# ProstheticController.net
KiCad netlist of a schematic drawn in Altium Designer
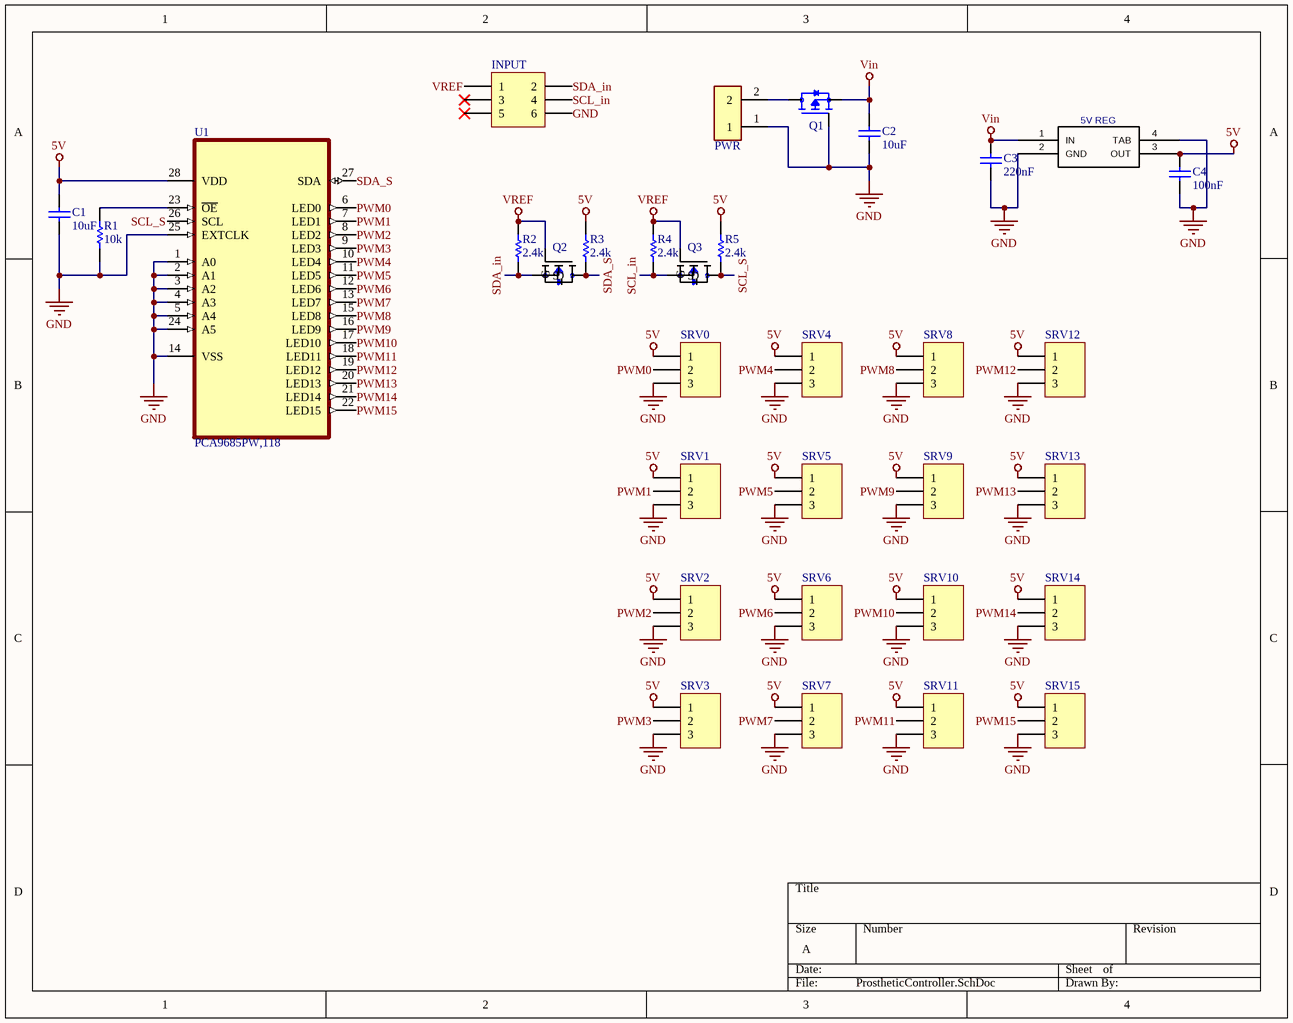
[diagram p0: ProstheticController.SchDoc]

(export (version "E")
  (design (tool "Eeschema 10.0.6"))
  (components
    (comp (ref "5V REG")
      (value "LM340SX-5.0/NOPB")
      (footprint "TS3B_TEX")
      (libsource (lib "5V_REG") (part "LM340SX-5.0/NOPB"))
    )
    (comp (ref "C1")
      (value "10uF")
      (footprint "0805-CAP")
      (description "Capacitor")
      (libsource (lib "Cap") (part "Cap"))
    )
    (comp (ref "C2")
      (value "10uF")
      (footprint "0805-CAP")
      (description "Capacitor")
      (libsource (lib "Cap") (part "Cap"))
    )
    (comp (ref "C3")
      (value "220nF")
      (footprint "0805-CAP")
      (description "Capacitor")
      (libsource (lib "Cap") (part "Cap"))
    )
    (comp (ref "C4")
      (value "100nF")
      (footprint "0805-CAP")
      (description "Capacitor")
      (libsource (lib "Cap") (part "Cap"))
    )
    (comp (ref "INPUT")
      (value "Header 3X2")
      (footprint "HDR2X3")
      (description "Header, 3-Pin, Dual row")
      (fields (field (name "PUBLISHER") "Altium Limited"))
      (libsource (lib "Miscellaneous Connectors") (part "Header 3X2"))
    )
    (comp (ref "PWR")
      (value "PWR")
      (footprint "OST_OSTTE020161")
      (fields (field (name "MP") "OSTTE020161") (field (name "MF") "On Shore"))
      (libsource (lib "Header2Pin") (part "OSTTE020161"))
    )
    (comp (ref "Q1")
      (value "AOD417")
      (footprint "DPAK228P994X240_3N")
      (description "P-Channel 30V 25A _Ta_ 2.5W _Ta_, 50W _Tc_ Surface Mount TO-252, _D-Pak_")
      (fields (field (name "MF") "Alpha &"))
      (libsource (lib "AOD417") (part "AOD417"))
    )
    (comp (ref "Q2")
      (value "BSS138")
      (footprint "*BSS138_BSS138(Primary)")
      (description "N-Channel 50V 220mA _Ta_ 360mW _Ta_ Surface Mount Die")
      (fields (field (name "MF") "MICROSS/On Semiconductor"))
      (libsource (lib "BSS138") (part "BSS138"))
    )
    (comp (ref "Q3")
      (value "BSS138")
      (footprint "*BSS138_BSS138(Primary)")
      (description "N-Channel 50V 220mA _Ta_ 360mW _Ta_ Surface Mount Die")
      (fields (field (name "MF") "MICROSS/On Semiconductor"))
      (libsource (lib "BSS138") (part "BSS138"))
    )
    (comp (ref "R1")
      (value "10k")
      (footprint "0805-RES")
      (description "Resistor")
      (libsource (lib "ResBasic") (part "ResBasic"))
    )
    (comp (ref "R2")
      (value "2.4k")
      (footprint "0805-RES")
      (description "Resistor")
      (libsource (lib "ResBasic") (part "ResBasic"))
    )
    (comp (ref "R3")
      (value "2.4k")
      (footprint "0805-RES")
      (description "Resistor")
      (libsource (lib "ResBasic") (part "ResBasic"))
    )
    (comp (ref "R4")
      (value "2.4k")
      (footprint "0805-RES")
      (description "Resistor")
      (libsource (lib "ResBasic") (part "ResBasic"))
    )
    (comp (ref "R5")
      (value "2.4k")
      (footprint "0805-RES")
      (description "Resistor")
      (libsource (lib "ResBasic") (part "ResBasic"))
    )
    (comp (ref "SRV0")
      (value "Header 3")
      (footprint "HDR1X3")
      (description "Header, 3-Pin")
      (fields (field (name "PUBLISHER") "Altium Limited"))
      (libsource (lib "Miscellaneous Connectors") (part "Header 3"))
    )
    (comp (ref "SRV1")
      (value "Header 3")
      (footprint "HDR1X3")
      (description "Header, 3-Pin")
      (fields (field (name "PUBLISHER") "Altium Limited"))
      (libsource (lib "Miscellaneous Connectors") (part "Header 3"))
    )
    (comp (ref "SRV2")
      (value "Header 3")
      (footprint "HDR1X3")
      (description "Header, 3-Pin")
      (fields (field (name "PUBLISHER") "Altium Limited"))
      (libsource (lib "Miscellaneous Connectors") (part "Header 3"))
    )
    (comp (ref "SRV3")
      (value "Header 3")
      (footprint "HDR1X3")
      (description "Header, 3-Pin")
      (fields (field (name "PUBLISHER") "Altium Limited"))
      (libsource (lib "Miscellaneous Connectors") (part "Header 3"))
    )
    (comp (ref "SRV4")
      (value "Header 3")
      (footprint "HDR1X3")
      (description "Header, 3-Pin")
      (fields (field (name "PUBLISHER") "Altium Limited"))
      (libsource (lib "Miscellaneous Connectors") (part "Header 3"))
    )
    (comp (ref "SRV5")
      (value "Header 3")
      (footprint "HDR1X3")
      (description "Header, 3-Pin")
      (fields (field (name "PUBLISHER") "Altium Limited"))
      (libsource (lib "Miscellaneous Connectors") (part "Header 3"))
    )
    (comp (ref "SRV6")
      (value "Header 3")
      (footprint "HDR1X3")
      (description "Header, 3-Pin")
      (fields (field (name "PUBLISHER") "Altium Limited"))
      (libsource (lib "Miscellaneous Connectors") (part "Header 3"))
    )
    (comp (ref "SRV7")
      (value "Header 3")
      (footprint "HDR1X3")
      (description "Header, 3-Pin")
      (fields (field (name "PUBLISHER") "Altium Limited"))
      (libsource (lib "Miscellaneous Connectors") (part "Header 3"))
    )
    (comp (ref "SRV8")
      (value "Header 3")
      (footprint "HDR1X3")
      (description "Header, 3-Pin")
      (fields (field (name "PUBLISHER") "Altium Limited"))
      (libsource (lib "Miscellaneous Connectors") (part "Header 3"))
    )
    (comp (ref "SRV9")
      (value "Header 3")
      (footprint "HDR1X3")
      (description "Header, 3-Pin")
      (fields (field (name "PUBLISHER") "Altium Limited"))
      (libsource (lib "Miscellaneous Connectors") (part "Header 3"))
    )
    (comp (ref "SRV10")
      (value "Header 3")
      (footprint "HDR1X3")
      (description "Header, 3-Pin")
      (fields (field (name "PUBLISHER") "Altium Limited"))
      (libsource (lib "Miscellaneous Connectors") (part "Header 3"))
    )
    (comp (ref "SRV11")
      (value "Header 3")
      (footprint "HDR1X3")
      (description "Header, 3-Pin")
      (fields (field (name "PUBLISHER") "Altium Limited"))
      (libsource (lib "Miscellaneous Connectors") (part "Header 3"))
    )
    (comp (ref "SRV12")
      (value "Header 3")
      (footprint "HDR1X3")
      (description "Header, 3-Pin")
      (fields (field (name "PUBLISHER") "Altium Limited"))
      (libsource (lib "Miscellaneous Connectors") (part "Header 3"))
    )
    (comp (ref "SRV13")
      (value "Header 3")
      (footprint "HDR1X3")
      (description "Header, 3-Pin")
      (fields (field (name "PUBLISHER") "Altium Limited"))
      (libsource (lib "Miscellaneous Connectors") (part "Header 3"))
    )
    (comp (ref "SRV14")
      (value "Header 3")
      (footprint "HDR1X3")
      (description "Header, 3-Pin")
      (fields (field (name "PUBLISHER") "Altium Limited"))
      (libsource (lib "Miscellaneous Connectors") (part "Header 3"))
    )
    (comp (ref "SRV15")
      (value "Header 3")
      (footprint "HDR1X3")
      (description "Header, 3-Pin")
      (fields (field (name "PUBLISHER") "Altium Limited"))
      (libsource (lib "Miscellaneous Connectors") (part "Header 3"))
    )
    (comp (ref "U1")
      (value "PCA9685PW,118")
      (footprint "SOP65P640X110-28N")
      (description "LED Driver IC 16 Output Linear PWM Dimming 25mA 28-TSSOP")
      (fields (field (name "DIGI-KEY_PART_NUMBER") "568-11925-1-ND") (field (name "MF") "NXP USA"))
      (libsource (lib "SERVO_DRIVER") (part "PCA9685PW,118"))
    )
  )
  (nets
    (net (code "1") (name "/PWM0") (class "Default")
      (node (ref "SRV0") (pin "2") (pinfunction "2_2") (pintype "passive"))
      (node (ref "U1") (pin "6") (pinfunction "LED0_6") (pintype "output"))
    )
    (net (code "2") (name "/PWM1") (class "Default")
      (node (ref "SRV1") (pin "2") (pinfunction "2_2") (pintype "passive"))
      (node (ref "U1") (pin "7") (pinfunction "LED1_7") (pintype "output"))
    )
    (net (code "3") (name "/PWM2") (class "Default")
      (node (ref "SRV2") (pin "2") (pinfunction "2_2") (pintype "passive"))
      (node (ref "U1") (pin "8") (pinfunction "LED2_8") (pintype "output"))
    )
    (net (code "4") (name "/PWM3") (class "Default")
      (node (ref "SRV3") (pin "2") (pinfunction "2_2") (pintype "passive"))
      (node (ref "U1") (pin "9") (pinfunction "LED3_9") (pintype "output"))
    )
    (net (code "5") (name "/PWM4") (class "Default")
      (node (ref "SRV4") (pin "2") (pinfunction "2_2") (pintype "passive"))
      (node (ref "U1") (pin "10") (pinfunction "LED4_10") (pintype "output"))
    )
    (net (code "6") (name "/PWM5") (class "Default")
      (node (ref "SRV5") (pin "2") (pinfunction "2_2") (pintype "passive"))
      (node (ref "U1") (pin "11") (pinfunction "LED5_11") (pintype "output"))
    )
    (net (code "7") (name "/PWM6") (class "Default")
      (node (ref "SRV6") (pin "2") (pinfunction "2_2") (pintype "passive"))
      (node (ref "U1") (pin "12") (pinfunction "LED6_12") (pintype "output"))
    )
    (net (code "8") (name "/PWM7") (class "Default")
      (node (ref "SRV7") (pin "2") (pinfunction "2_2") (pintype "passive"))
      (node (ref "U1") (pin "13") (pinfunction "LED7_13") (pintype "output"))
    )
    (net (code "9") (name "/PWM8") (class "Default")
      (node (ref "SRV8") (pin "2") (pinfunction "2_2") (pintype "passive"))
      (node (ref "U1") (pin "15") (pinfunction "LED8_15") (pintype "output"))
    )
    (net (code "10") (name "/PWM9") (class "Default")
      (node (ref "SRV9") (pin "2") (pinfunction "2_2") (pintype "passive"))
      (node (ref "U1") (pin "16") (pinfunction "LED9_16") (pintype "output"))
    )
    (net (code "11") (name "/PWM10") (class "Default")
      (node (ref "SRV10") (pin "2") (pinfunction "2_2") (pintype "passive"))
      (node (ref "U1") (pin "17") (pinfunction "LED10_17") (pintype "output"))
    )
    (net (code "12") (name "/PWM11") (class "Default")
      (node (ref "SRV11") (pin "2") (pinfunction "2_2") (pintype "passive"))
      (node (ref "U1") (pin "18") (pinfunction "LED11_18") (pintype "output"))
    )
    (net (code "13") (name "/PWM12") (class "Default")
      (node (ref "SRV12") (pin "2") (pinfunction "2_2") (pintype "passive"))
      (node (ref "U1") (pin "19") (pinfunction "LED12_19") (pintype "output"))
    )
    (net (code "14") (name "/PWM13") (class "Default")
      (node (ref "SRV13") (pin "2") (pinfunction "2_2") (pintype "passive"))
      (node (ref "U1") (pin "20") (pinfunction "LED13_20") (pintype "output"))
    )
    (net (code "15") (name "/PWM14") (class "Default")
      (node (ref "SRV14") (pin "2") (pinfunction "2_2") (pintype "passive"))
      (node (ref "U1") (pin "21") (pinfunction "LED14_21") (pintype "output"))
    )
    (net (code "16") (name "/PWM15") (class "Default")
      (node (ref "SRV15") (pin "2") (pinfunction "2_2") (pintype "passive"))
      (node (ref "U1") (pin "22") (pinfunction "LED15_22") (pintype "output"))
    )
    (net (code "17") (name "/SCL_S") (class "Default")
      (node (ref "Q3") (pin "D") (pinfunction "D_D") (pintype "passive"))
      (node (ref "R5") (pin "1") (pinfunction "1_1") (pintype "passive"))
      (node (ref "U1") (pin "26") (pinfunction "SCL_26") (pintype "input"))
    )
    (net (code "18") (name "/SCL_in") (class "Default")
      (node (ref "INPUT") (pin "4") (pinfunction "4_4") (pintype "passive"))
      (node (ref "Q3") (pin "S") (pinfunction "S_S") (pintype "passive"))
      (node (ref "R4") (pin "1") (pinfunction "1_1") (pintype "passive"))
    )
    (net (code "19") (name "/SDA_S") (class "Default")
      (node (ref "Q2") (pin "D") (pinfunction "D_D") (pintype "passive"))
      (node (ref "R3") (pin "1") (pinfunction "1_1") (pintype "passive"))
      (node (ref "U1") (pin "27") (pinfunction "SDA_27") (pintype "bidirectional"))
    )
    (net (code "20") (name "/SDA_in") (class "Default")
      (node (ref "INPUT") (pin "2") (pinfunction "2_2") (pintype "passive"))
      (node (ref "Q2") (pin "S") (pinfunction "S_S") (pintype "passive"))
      (node (ref "R2") (pin "1") (pinfunction "1_1") (pintype "passive"))
    )
    (net (code "21") (name "5V") (class "Default")
      (node (ref "5V REG") (pin "3") (pinfunction "OUT_3") (pintype "power_in"))
      (node (ref "C1") (pin "2") (pinfunction "2_2") (pintype "passive"))
      (node (ref "C4") (pin "2") (pinfunction "2_2") (pintype "passive"))
      (node (ref "R3") (pin "2") (pinfunction "2_2") (pintype "passive"))
      (node (ref "R5") (pin "2") (pinfunction "2_2") (pintype "passive"))
      (node (ref "SRV0") (pin "1") (pinfunction "1_1") (pintype "passive"))
      (node (ref "SRV1") (pin "1") (pinfunction "1_1") (pintype "passive"))
      (node (ref "SRV10") (pin "1") (pinfunction "1_1") (pintype "passive"))
      (node (ref "SRV11") (pin "1") (pinfunction "1_1") (pintype "passive"))
      (node (ref "SRV12") (pin "1") (pinfunction "1_1") (pintype "passive"))
      (node (ref "SRV13") (pin "1") (pinfunction "1_1") (pintype "passive"))
      (node (ref "SRV14") (pin "1") (pinfunction "1_1") (pintype "passive"))
      (node (ref "SRV15") (pin "1") (pinfunction "1_1") (pintype "passive"))
      (node (ref "SRV2") (pin "1") (pinfunction "1_1") (pintype "passive"))
      (node (ref "SRV3") (pin "1") (pinfunction "1_1") (pintype "passive"))
      (node (ref "SRV4") (pin "1") (pinfunction "1_1") (pintype "passive"))
      (node (ref "SRV5") (pin "1") (pinfunction "1_1") (pintype "passive"))
      (node (ref "SRV6") (pin "1") (pinfunction "1_1") (pintype "passive"))
      (node (ref "SRV7") (pin "1") (pinfunction "1_1") (pintype "passive"))
      (node (ref "SRV8") (pin "1") (pinfunction "1_1") (pintype "passive"))
      (node (ref "SRV9") (pin "1") (pinfunction "1_1") (pintype "passive"))
      (node (ref "U1") (pin "28") (pinfunction "VDD_28") (pintype "power_in"))
    )
    (net (code "22") (name "GND") (class "Default")
      (node (ref "5V REG") (pin "2") (pinfunction "GND_2") (pintype "power_in"))
      (node (ref "5V REG") (pin "4") (pinfunction "TAB_4") (pintype "power_in"))
      (node (ref "C1") (pin "1") (pinfunction "1_1") (pintype "passive"))
      (node (ref "C2") (pin "1") (pinfunction "1_1") (pintype "passive"))
      (node (ref "C3") (pin "1") (pinfunction "1_1") (pintype "passive"))
      (node (ref "C4") (pin "1") (pinfunction "1_1") (pintype "passive"))
      (node (ref "INPUT") (pin "6") (pinfunction "6_6") (pintype "passive"))
      (node (ref "PWR") (pin "1") (pinfunction "1_1") (pintype "passive"))
      (node (ref "Q1") (pin "1") (pinfunction "G_1") (pintype "passive"))
      (node (ref "R1") (pin "1") (pinfunction "1_1") (pintype "passive"))
      (node (ref "SRV0") (pin "3") (pinfunction "3_3") (pintype "passive"))
      (node (ref "SRV1") (pin "3") (pinfunction "3_3") (pintype "passive"))
      (node (ref "SRV10") (pin "3") (pinfunction "3_3") (pintype "passive"))
      (node (ref "SRV11") (pin "3") (pinfunction "3_3") (pintype "passive"))
      (node (ref "SRV12") (pin "3") (pinfunction "3_3") (pintype "passive"))
      (node (ref "SRV13") (pin "3") (pinfunction "3_3") (pintype "passive"))
      (node (ref "SRV14") (pin "3") (pinfunction "3_3") (pintype "passive"))
      (node (ref "SRV15") (pin "3") (pinfunction "3_3") (pintype "passive"))
      (node (ref "SRV2") (pin "3") (pinfunction "3_3") (pintype "passive"))
      (node (ref "SRV3") (pin "3") (pinfunction "3_3") (pintype "passive"))
      (node (ref "SRV4") (pin "3") (pinfunction "3_3") (pintype "passive"))
      (node (ref "SRV5") (pin "3") (pinfunction "3_3") (pintype "passive"))
      (node (ref "SRV6") (pin "3") (pinfunction "3_3") (pintype "passive"))
      (node (ref "SRV7") (pin "3") (pinfunction "3_3") (pintype "passive"))
      (node (ref "SRV8") (pin "3") (pinfunction "3_3") (pintype "passive"))
      (node (ref "SRV9") (pin "3") (pinfunction "3_3") (pintype "passive"))
      (node (ref "U1") (pin "1") (pinfunction "A0_1") (pintype "input"))
      (node (ref "U1") (pin "14") (pinfunction "VSS_14") (pintype "passive"))
      (node (ref "U1") (pin "2") (pinfunction "A1_2") (pintype "input"))
      (node (ref "U1") (pin "24") (pinfunction "A5_24") (pintype "input"))
      (node (ref "U1") (pin "25") (pinfunction "EXTCLK_25") (pintype "input"))
      (node (ref "U1") (pin "3") (pinfunction "A2_3") (pintype "input"))
      (node (ref "U1") (pin "4") (pinfunction "A3_4") (pintype "input"))
      (node (ref "U1") (pin "5") (pinfunction "A4_5") (pintype "input"))
    )
    (net (code "23") (name "Net-(Q1-D)") (class "Default")
      (node (ref "PWR") (pin "2") (pinfunction "2_2") (pintype "passive"))
      (node (ref "Q1") (pin "4") (pinfunction "D_4") (pintype "passive"))
    )
    (net (code "24") (name "Net-(U1-~{OE})") (class "Default")
      (node (ref "R1") (pin "2") (pinfunction "2_2") (pintype "passive"))
      (node (ref "U1") (pin "23") (pinfunction "~{OE}_23") (pintype "input"))
    )
    (net (code "25") (name "VREF") (class "Default")
      (node (ref "INPUT") (pin "1") (pinfunction "1_1") (pintype "passive"))
      (node (ref "Q2") (pin "G") (pinfunction "G_G") (pintype "passive"))
      (node (ref "Q3") (pin "G") (pinfunction "G_G") (pintype "passive"))
      (node (ref "R2") (pin "2") (pinfunction "2_2") (pintype "passive"))
      (node (ref "R4") (pin "2") (pinfunction "2_2") (pintype "passive"))
    )
    (net (code "26") (name "Vin") (class "Default")
      (node (ref "5V REG") (pin "1") (pinfunction "IN_1") (pintype "power_in"))
      (node (ref "C2") (pin "2") (pinfunction "2_2") (pintype "passive"))
      (node (ref "C3") (pin "2") (pinfunction "2_2") (pintype "passive"))
      (node (ref "Q1") (pin "3") (pinfunction "S_3") (pintype "passive"))
    )
    (net (code "27") (name "unconnected-(INPUT-Pad3)") (class "Default")
      (node (ref "INPUT") (pin "3") (pinfunction "3_3") (pintype "passive+no_connect"))
    )
    (net (code "28") (name "unconnected-(INPUT-Pad5)") (class "Default")
      (node (ref "INPUT") (pin "5") (pinfunction "5_5") (pintype "passive+no_connect"))
    )
  )
)
